# Interfaces_and_Connectors_-_Sensors.net
KiCad netlist of a schematic drawn in Altium Designer
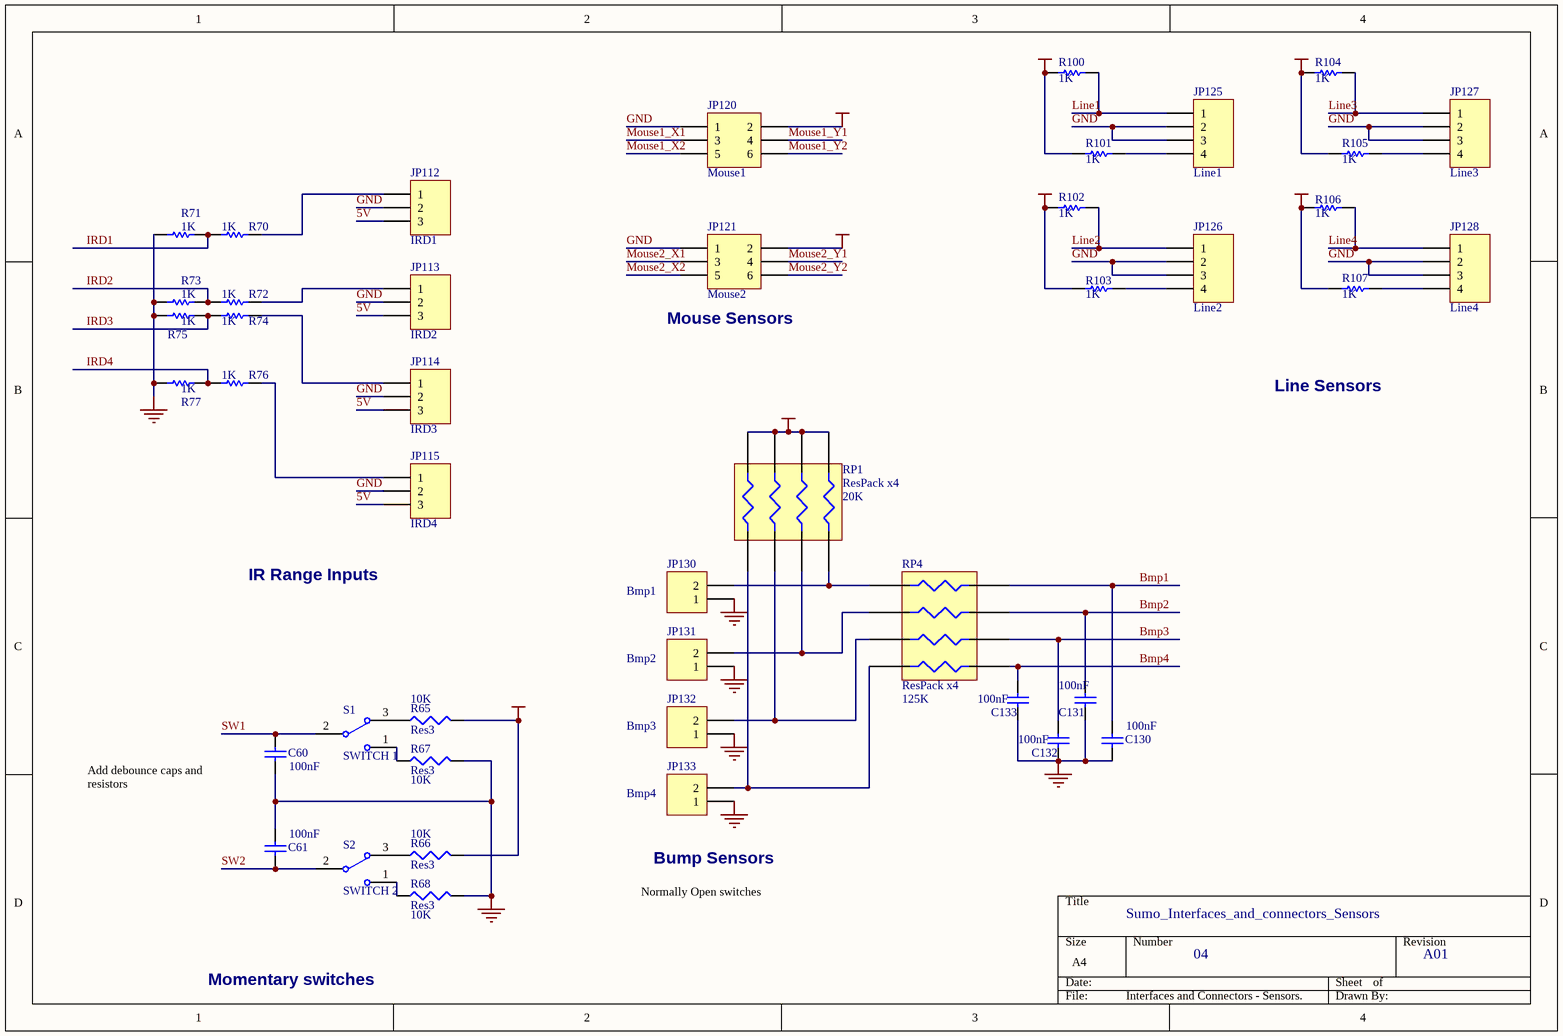
[diagram p0: Interfaces and Connectors - Sensors.SCHDOC]

(export (version "E")
  (design (tool "Eeschema 10.0.6"))
  (components
    (comp (ref "C60")
      (value "100nF")
      (footprint "CR2012-0805")
      (description "Capacitor (Semiconductor SIM Model)")
      (fields (field (name "Comment") "Cap Semi") (field (name "PUBLISHER") "Altium Limited"))
      (libsource (lib "Miscellaneous Devices") (part "Cap Semi"))
    )
    (comp (ref "C61")
      (value "100nF")
      (footprint "CR2012-0805")
      (description "Capacitor (Semiconductor SIM Model)")
      (fields (field (name "Comment") "Cap Semi") (field (name "PUBLISHER") "Altium Limited"))
      (libsource (lib "Miscellaneous Devices") (part "Cap Semi"))
    )
    (comp (ref "C130")
      (value "100nF")
      (footprint "CR2012-0805")
      (description "Capacitor (Semiconductor SIM Model)")
      (fields (field (name "Comment") "Cap Semi") (field (name "PUBLISHER") "Altium Limited"))
      (libsource (lib "Miscellaneous Devices") (part "Cap Semi"))
    )
    (comp (ref "C131")
      (value "100nF")
      (footprint "CR2012-0805")
      (description "Capacitor (Semiconductor SIM Model)")
      (fields (field (name "Comment") "Cap Semi") (field (name "PUBLISHER") "Altium Limited"))
      (libsource (lib "Miscellaneous Devices") (part "Cap Semi"))
    )
    (comp (ref "C132")
      (value "100nF")
      (footprint "CR2012-0805")
      (description "Capacitor (Semiconductor SIM Model)")
      (fields (field (name "Comment") "Cap Semi") (field (name "PUBLISHER") "Altium Limited"))
      (libsource (lib "Miscellaneous Devices") (part "Cap Semi"))
    )
    (comp (ref "C133")
      (value "100nF")
      (footprint "CR2012-0805")
      (description "Capacitor (Semiconductor SIM Model)")
      (fields (field (name "Comment") "Cap Semi") (field (name "PUBLISHER") "Altium Limited"))
      (libsource (lib "Miscellaneous Devices") (part "Cap Semi"))
    )
    (comp (ref "JP112")
      (value "IRD1")
      (footprint "ZHR 1x3 1.5mm")
      (description "Header, 3-Pin")
      (fields (field (name "PUBLISHER") "Altium Limited"))
      (libsource (lib "Miscellaneous Connectors") (part "MHDR1X3"))
    )
    (comp (ref "JP113")
      (value "IRD2")
      (footprint "ZHR 1x3 1.5mm")
      (description "Header, 3-Pin")
      (fields (field (name "PUBLISHER") "Altium Limited"))
      (libsource (lib "Miscellaneous Connectors") (part "MHDR1X3"))
    )
    (comp (ref "JP114")
      (value "IRD3")
      (footprint "ZHR 1x3 1.5mm")
      (description "Header, 3-Pin")
      (fields (field (name "PUBLISHER") "Altium Limited"))
      (libsource (lib "Miscellaneous Connectors") (part "MHDR1X3"))
    )
    (comp (ref "JP115")
      (value "IRD4")
      (footprint "ZHR 1x3 1.5mm")
      (description "Header, 3-Pin")
      (fields (field (name "PUBLISHER") "Altium Limited"))
      (libsource (lib "Miscellaneous Connectors") (part "MHDR1X3"))
    )
    (comp (ref "JP120")
      (value "Mouse1")
      (footprint "PHR 1x6 2mm")
      (description "Header, 3-Pin, Dual row")
      (fields (field (name "PUBLISHER") "Altium Limited"))
      (libsource (lib "Miscellaneous Connectors") (part "Header 3X2"))
    )
    (comp (ref "JP121")
      (value "Mouse2")
      (footprint "PHR 1x6 2mm")
      (description "Header, 3-Pin, Dual row")
      (fields (field (name "PUBLISHER") "Altium Limited"))
      (libsource (lib "Miscellaneous Connectors") (part "Header 3X2"))
    )
    (comp (ref "JP125")
      (value "Line1")
      (footprint "EHR 1x4 2.5mm")
      (description "Header, 4-Pin, Right Angle")
      (fields (field (name "PUBLISHER") "Altium Limited"))
      (libsource (lib "Miscellaneous Connectors") (part "Header 4H"))
    )
    (comp (ref "JP126")
      (value "Line2")
      (footprint "EHR 1x4 2.5mm")
      (description "Header, 4-Pin, Right Angle")
      (fields (field (name "PUBLISHER") "Altium Limited"))
      (libsource (lib "Miscellaneous Connectors") (part "Header 4H"))
    )
    (comp (ref "JP127")
      (value "Line3")
      (footprint "EHR 1x4 2.5mm")
      (description "Header, 4-Pin, Right Angle")
      (fields (field (name "PUBLISHER") "Altium Limited"))
      (libsource (lib "Miscellaneous Connectors") (part "Header 4H"))
    )
    (comp (ref "JP128")
      (value "Line4")
      (footprint "EHR 1x4 2.5mm")
      (description "Header, 4-Pin, Right Angle")
      (fields (field (name "PUBLISHER") "Altium Limited"))
      (libsource (lib "Miscellaneous Connectors") (part "Header 4H"))
    )
    (comp (ref "JP130")
      (value "Bmp1")
      (footprint "KK 1x2 2.54mm")
      (description "Header, 2-Pin")
      (fields (field (name "PUBLISHER") "Altium Limited"))
      (libsource (lib "Miscellaneous Connectors") (part "Header 2"))
    )
    (comp (ref "JP131")
      (value "Bmp2")
      (footprint "KK 1x2 2.54mm")
      (description "Header, 2-Pin")
      (fields (field (name "PUBLISHER") "Altium Limited"))
      (libsource (lib "Miscellaneous Connectors") (part "Header 2"))
    )
    (comp (ref "JP132")
      (value "Bmp3")
      (footprint "KK 1x2 2.54mm")
      (description "Header, 2-Pin")
      (fields (field (name "PUBLISHER") "Altium Limited"))
      (libsource (lib "Miscellaneous Connectors") (part "Header 2"))
    )
    (comp (ref "JP133")
      (value "Bmp4")
      (footprint "KK 1x2 2.54mm")
      (description "Header, 2-Pin")
      (fields (field (name "PUBLISHER") "Altium Limited"))
      (libsource (lib "Miscellaneous Connectors") (part "Header 2"))
    )
    (comp (ref "R65")
      (value "Res3")
      (footprint "R2012-0805")
      (description "Resistor")
      (fields (field (name "ALTIUM_VALUE") "10K") (field (name "PUBLISHER") "Altium Limited"))
      (libsource (lib "Miscellaneous Devices") (part "Res3"))
    )
    (comp (ref "R66")
      (value "Res3")
      (footprint "R2012-0805")
      (description "Resistor")
      (fields (field (name "ALTIUM_VALUE") "10K") (field (name "PUBLISHER") "Altium Limited"))
      (libsource (lib "Miscellaneous Devices") (part "Res3"))
    )
    (comp (ref "R67")
      (value "Res3")
      (footprint "R2012-0805")
      (description "Resistor")
      (fields (field (name "ALTIUM_VALUE") "10K") (field (name "PUBLISHER") "Altium Limited"))
      (libsource (lib "Miscellaneous Devices") (part "Res3"))
    )
    (comp (ref "R68")
      (value "Res3")
      (footprint "R2012-0805")
      (description "Resistor")
      (fields (field (name "ALTIUM_VALUE") "10K") (field (name "PUBLISHER") "Altium Limited"))
      (libsource (lib "Miscellaneous Devices") (part "Res3"))
    )
    (comp (ref "R70")
      (value "1K")
      (footprint "CR2012-0805")
      (description "Resistor")
      (fields (field (name "Comment") "Res1") (field (name "PUBLISHER") "Altium Limited"))
      (libsource (lib "Miscellaneous Devices") (part "Res1"))
    )
    (comp (ref "R71")
      (value "1K")
      (footprint "CR2012-0805")
      (description "Resistor")
      (fields (field (name "Comment") "Res1") (field (name "PUBLISHER") "Altium Limited"))
      (libsource (lib "Miscellaneous Devices") (part "Res1"))
    )
    (comp (ref "R72")
      (value "1K")
      (footprint "CR2012-0805")
      (description "Resistor")
      (fields (field (name "Comment") "Res1") (field (name "PUBLISHER") "Altium Limited"))
      (libsource (lib "Miscellaneous Devices") (part "Res1"))
    )
    (comp (ref "R73")
      (value "1K")
      (footprint "CR2012-0805")
      (description "Resistor")
      (fields (field (name "Comment") "Res1") (field (name "PUBLISHER") "Altium Limited"))
      (libsource (lib "Miscellaneous Devices") (part "Res1"))
    )
    (comp (ref "R74")
      (value "1K")
      (footprint "CR2012-0805")
      (description "Resistor")
      (fields (field (name "Comment") "Res1") (field (name "PUBLISHER") "Altium Limited"))
      (libsource (lib "Miscellaneous Devices") (part "Res1"))
    )
    (comp (ref "R75")
      (value "1K")
      (footprint "CR2012-0805")
      (description "Resistor")
      (fields (field (name "Comment") "Res1") (field (name "PUBLISHER") "Altium Limited"))
      (libsource (lib "Miscellaneous Devices") (part "Res1"))
    )
    (comp (ref "R76")
      (value "1K")
      (footprint "CR2012-0805")
      (description "Resistor")
      (fields (field (name "Comment") "Res1") (field (name "PUBLISHER") "Altium Limited"))
      (libsource (lib "Miscellaneous Devices") (part "Res1"))
    )
    (comp (ref "R77")
      (value "1K")
      (footprint "CR2012-0805")
      (description "Resistor")
      (fields (field (name "Comment") "Res1") (field (name "PUBLISHER") "Altium Limited"))
      (libsource (lib "Miscellaneous Devices") (part "Res1"))
    )
    (comp (ref "R100")
      (value "1K")
      (footprint "R2012-0805")
      (description "Resistor")
      (fields (field (name "Comment") "Res1") (field (name "PUBLISHER") "Altium Limited"))
      (libsource (lib "Miscellaneous Devices") (part "Res1"))
    )
    (comp (ref "R101")
      (value "1K")
      (footprint "R2012-0805")
      (description "Resistor")
      (fields (field (name "Comment") "Res1") (field (name "PUBLISHER") "Altium Limited"))
      (libsource (lib "Miscellaneous Devices") (part "Res1"))
    )
    (comp (ref "R102")
      (value "1K")
      (footprint "R2012-0805")
      (description "Resistor")
      (fields (field (name "Comment") "Res1") (field (name "PUBLISHER") "Altium Limited"))
      (libsource (lib "Miscellaneous Devices") (part "Res1"))
    )
    (comp (ref "R103")
      (value "1K")
      (footprint "R2012-0805")
      (description "Resistor")
      (fields (field (name "Comment") "Res1") (field (name "PUBLISHER") "Altium Limited"))
      (libsource (lib "Miscellaneous Devices") (part "Res1"))
    )
    (comp (ref "R104")
      (value "1K")
      (footprint "R2012-0805")
      (description "Resistor")
      (fields (field (name "Comment") "Res1") (field (name "PUBLISHER") "Altium Limited"))
      (libsource (lib "Miscellaneous Devices") (part "Res1"))
    )
    (comp (ref "R105")
      (value "1K")
      (footprint "R2012-0805")
      (description "Resistor")
      (fields (field (name "Comment") "Res1") (field (name "PUBLISHER") "Altium Limited"))
      (libsource (lib "Miscellaneous Devices") (part "Res1"))
    )
    (comp (ref "R106")
      (value "1K")
      (footprint "R2012-0805")
      (description "Resistor")
      (fields (field (name "Comment") "Res1") (field (name "PUBLISHER") "Altium Limited"))
      (libsource (lib "Miscellaneous Devices") (part "Res1"))
    )
    (comp (ref "R107")
      (value "1K")
      (footprint "R2012-0805")
      (description "Resistor")
      (fields (field (name "Comment") "Res1") (field (name "PUBLISHER") "Altium Limited"))
      (libsource (lib "Miscellaneous Devices") (part "Res1"))
    )
    (comp (ref "RP1")
      (value "ResPack x4")
      (footprint "4x0805 Resistor pack")
      (fields (field (name "ALTIUM_VALUE") "20K"))
      (libsource (lib "Sumo") (part "ResPack x4"))
    )
    (comp (ref "RP4")
      (value "ResPack x4")
      (footprint "4x0805 Resistor pack")
      (fields (field (name "ALTIUM_VALUE") "125K"))
      (libsource (lib "") (part "ResPack x4_1"))
    )
    (comp (ref "S1")
      (value "SWITCH 1")
      (footprint "SW SPDT")
      (description "SPDT Subminiature Toggle Switch, Right Angle Mounting, Vertical Actuation")
      (fields (field (name "PUBLISHER") "Altium Limited"))
      (libsource (lib "Miscellaneous Devices") (part "SW-SPDT"))
    )
    (comp (ref "S2")
      (value "SWITCH 2")
      (footprint "SW SPDT")
      (description "SPDT Subminiature Toggle Switch, Right Angle Mounting, Vertical Actuation")
      (fields (field (name "PUBLISHER") "Altium Limited"))
      (libsource (lib "Miscellaneous Devices") (part "SW-SPDT"))
    )
  )
  (nets
    (net (code "1") (name "/Bmp1") (class "Default")
      (node (ref "C130") (pin "2") (pinfunction "2_2") (pintype "passive"))
      (node (ref "RP4") (pin "8") (pintype "passive"))
    )
    (net (code "2") (name "/Bmp2") (class "Default")
      (node (ref "C131") (pin "2") (pinfunction "2_2") (pintype "passive"))
      (node (ref "RP4") (pin "7") (pintype "passive"))
    )
    (net (code "3") (name "/Bmp3") (class "Default")
      (node (ref "C132") (pin "2") (pinfunction "2_2") (pintype "passive"))
      (node (ref "RP4") (pin "6") (pintype "passive"))
    )
    (net (code "4") (name "/Bmp4") (class "Default")
      (node (ref "C133") (pin "2") (pinfunction "2_2") (pintype "passive"))
      (node (ref "RP4") (pin "5") (pintype "passive"))
    )
    (net (code "5") (name "/IRD1") (class "Default")
      (node (ref "R70") (pin "1") (pinfunction "1_1") (pintype "passive"))
      (node (ref "R71") (pin "2") (pinfunction "2_2") (pintype "passive"))
    )
    (net (code "6") (name "/IRD2") (class "Default")
      (node (ref "R72") (pin "1") (pinfunction "1_1") (pintype "passive"))
      (node (ref "R73") (pin "2") (pinfunction "2_2") (pintype "passive"))
    )
    (net (code "7") (name "/IRD3") (class "Default")
      (node (ref "R74") (pin "1") (pinfunction "1_1") (pintype "passive"))
      (node (ref "R75") (pin "2") (pinfunction "2_2") (pintype "passive"))
    )
    (net (code "8") (name "/IRD4") (class "Default")
      (node (ref "R76") (pin "1") (pinfunction "1_1") (pintype "passive"))
      (node (ref "R77") (pin "2") (pinfunction "2_2") (pintype "passive"))
    )
    (net (code "9") (name "/Line1") (class "Default")
      (node (ref "JP125") (pin "1") (pinfunction "1_1") (pintype "passive"))
      (node (ref "R100") (pin "2") (pinfunction "2_2") (pintype "passive"))
    )
    (net (code "10") (name "/Line2") (class "Default")
      (node (ref "JP126") (pin "1") (pinfunction "1_1") (pintype "passive"))
      (node (ref "R102") (pin "2") (pinfunction "2_2") (pintype "passive"))
    )
    (net (code "11") (name "/Line3") (class "Default")
      (node (ref "JP127") (pin "1") (pinfunction "1_1") (pintype "passive"))
      (node (ref "R104") (pin "2") (pinfunction "2_2") (pintype "passive"))
    )
    (net (code "12") (name "/Line4") (class "Default")
      (node (ref "JP128") (pin "1") (pinfunction "1_1") (pintype "passive"))
      (node (ref "R106") (pin "2") (pinfunction "2_2") (pintype "passive"))
    )
    (net (code "13") (name "/Mouse1_X1") (class "Default")
      (node (ref "JP120") (pin "3") (pinfunction "3_3") (pintype "passive"))
    )
    (net (code "14") (name "/Mouse1_X2") (class "Default")
      (node (ref "JP120") (pin "5") (pinfunction "5_5") (pintype "passive"))
    )
    (net (code "15") (name "/Mouse1_Y1") (class "Default")
      (node (ref "JP120") (pin "4") (pinfunction "4_4") (pintype "passive"))
    )
    (net (code "16") (name "/Mouse1_Y2") (class "Default")
      (node (ref "JP120") (pin "6") (pinfunction "6_6") (pintype "passive"))
    )
    (net (code "17") (name "/Mouse2_X1") (class "Default")
      (node (ref "JP121") (pin "3") (pinfunction "3_3") (pintype "passive"))
    )
    (net (code "18") (name "/Mouse2_X2") (class "Default")
      (node (ref "JP121") (pin "5") (pinfunction "5_5") (pintype "passive"))
    )
    (net (code "19") (name "/Mouse2_Y1") (class "Default")
      (node (ref "JP121") (pin "4") (pinfunction "4_4") (pintype "passive"))
    )
    (net (code "20") (name "/Mouse2_Y2") (class "Default")
      (node (ref "JP121") (pin "6") (pinfunction "6_6") (pintype "passive"))
    )
    (net (code "21") (name "/SW1") (class "Default")
      (node (ref "C60") (pin "2") (pinfunction "2_2") (pintype "passive"))
      (node (ref "S1") (pin "2") (pintype "passive"))
    )
    (net (code "22") (name "/SW2") (class "Default")
      (node (ref "C61") (pin "1") (pinfunction "1_1") (pintype "passive"))
      (node (ref "S2") (pin "2") (pintype "passive"))
    )
    (net (code "23") (name "5V") (class "Default")
      (node (ref "JP112") (pin "3") (pinfunction "3_3") (pintype "passive"))
      (node (ref "JP113") (pin "3") (pinfunction "3_3") (pintype "passive"))
      (node (ref "JP114") (pin "3") (pinfunction "3_3") (pintype "passive"))
      (node (ref "JP115") (pin "3") (pinfunction "3_3") (pintype "passive"))
      (node (ref "JP120") (pin "2") (pinfunction "2_2") (pintype "passive"))
      (node (ref "JP121") (pin "2") (pinfunction "2_2") (pintype "passive"))
      (node (ref "R100") (pin "1") (pinfunction "1_1") (pintype "passive"))
      (node (ref "R101") (pin "1") (pinfunction "1_1") (pintype "passive"))
      (node (ref "R102") (pin "1") (pinfunction "1_1") (pintype "passive"))
      (node (ref "R103") (pin "1") (pinfunction "1_1") (pintype "passive"))
      (node (ref "R104") (pin "1") (pinfunction "1_1") (pintype "passive"))
      (node (ref "R105") (pin "1") (pinfunction "1_1") (pintype "passive"))
      (node (ref "R106") (pin "1") (pinfunction "1_1") (pintype "passive"))
      (node (ref "R107") (pin "1") (pinfunction "1_1") (pintype "passive"))
      (node (ref "R65") (pin "2") (pinfunction "2_2") (pintype "passive"))
      (node (ref "R66") (pin "2") (pinfunction "2_2") (pintype "passive"))
      (node (ref "RP1") (pin "5") (pintype "passive"))
      (node (ref "RP1") (pin "6") (pintype "passive"))
      (node (ref "RP1") (pin "7") (pintype "passive"))
      (node (ref "RP1") (pin "8") (pintype "passive"))
    )
    (net (code "24") (name "GND") (class "Default")
      (node (ref "C130") (pin "1") (pinfunction "1_1") (pintype "passive"))
      (node (ref "C131") (pin "1") (pinfunction "1_1") (pintype "passive"))
      (node (ref "C132") (pin "1") (pinfunction "1_1") (pintype "passive"))
      (node (ref "C133") (pin "1") (pinfunction "1_1") (pintype "passive"))
      (node (ref "C60") (pin "1") (pinfunction "1_1") (pintype "passive"))
      (node (ref "C61") (pin "2") (pinfunction "2_2") (pintype "passive"))
      (node (ref "JP112") (pin "2") (pinfunction "2_2") (pintype "passive"))
      (node (ref "JP113") (pin "2") (pinfunction "2_2") (pintype "passive"))
      (node (ref "JP114") (pin "2") (pinfunction "2_2") (pintype "passive"))
      (node (ref "JP115") (pin "2") (pinfunction "2_2") (pintype "passive"))
      (node (ref "JP120") (pin "1") (pinfunction "1_1") (pintype "passive"))
      (node (ref "JP121") (pin "1") (pinfunction "1_1") (pintype "passive"))
      (node (ref "JP125") (pin "2") (pinfunction "2_2") (pintype "passive"))
      (node (ref "JP125") (pin "3") (pinfunction "3_3") (pintype "passive"))
      (node (ref "JP126") (pin "2") (pinfunction "2_2") (pintype "passive"))
      (node (ref "JP126") (pin "3") (pinfunction "3_3") (pintype "passive"))
      (node (ref "JP127") (pin "2") (pinfunction "2_2") (pintype "passive"))
      (node (ref "JP127") (pin "3") (pinfunction "3_3") (pintype "passive"))
      (node (ref "JP128") (pin "2") (pinfunction "2_2") (pintype "passive"))
      (node (ref "JP128") (pin "3") (pinfunction "3_3") (pintype "passive"))
      (node (ref "JP130") (pin "1") (pinfunction "1_1") (pintype "passive"))
      (node (ref "JP131") (pin "1") (pinfunction "1_1") (pintype "passive"))
      (node (ref "JP132") (pin "1") (pinfunction "1_1") (pintype "passive"))
      (node (ref "JP133") (pin "1") (pinfunction "1_1") (pintype "passive"))
      (node (ref "R67") (pin "2") (pinfunction "2_2") (pintype "passive"))
      (node (ref "R68") (pin "2") (pinfunction "2_2") (pintype "passive"))
      (node (ref "R71") (pin "1") (pinfunction "1_1") (pintype "passive"))
      (node (ref "R73") (pin "1") (pinfunction "1_1") (pintype "passive"))
      (node (ref "R75") (pin "1") (pinfunction "1_1") (pintype "passive"))
      (node (ref "R77") (pin "1") (pinfunction "1_1") (pintype "passive"))
    )
    (net (code "25") (name "Net-(JP112-Pad1)") (class "Default")
      (node (ref "JP112") (pin "1") (pinfunction "1_1") (pintype "passive"))
      (node (ref "R70") (pin "2") (pinfunction "2_2") (pintype "passive"))
    )
    (net (code "26") (name "Net-(JP113-Pad1)") (class "Default")
      (node (ref "JP113") (pin "1") (pinfunction "1_1") (pintype "passive"))
      (node (ref "R72") (pin "2") (pinfunction "2_2") (pintype "passive"))
    )
    (net (code "27") (name "Net-(JP114-Pad1)") (class "Default")
      (node (ref "JP114") (pin "1") (pinfunction "1_1") (pintype "passive"))
      (node (ref "R74") (pin "2") (pinfunction "2_2") (pintype "passive"))
    )
    (net (code "28") (name "Net-(JP115-Pad1)") (class "Default")
      (node (ref "JP115") (pin "1") (pinfunction "1_1") (pintype "passive"))
      (node (ref "R76") (pin "2") (pinfunction "2_2") (pintype "passive"))
    )
    (net (code "29") (name "Net-(JP125-Pad4)") (class "Default")
      (node (ref "JP125") (pin "4") (pinfunction "4_4") (pintype "passive"))
      (node (ref "R101") (pin "2") (pinfunction "2_2") (pintype "passive"))
    )
    (net (code "30") (name "Net-(JP126-Pad4)") (class "Default")
      (node (ref "JP126") (pin "4") (pinfunction "4_4") (pintype "passive"))
      (node (ref "R103") (pin "2") (pinfunction "2_2") (pintype "passive"))
    )
    (net (code "31") (name "Net-(JP127-Pad4)") (class "Default")
      (node (ref "JP127") (pin "4") (pinfunction "4_4") (pintype "passive"))
      (node (ref "R105") (pin "2") (pinfunction "2_2") (pintype "passive"))
    )
    (net (code "32") (name "Net-(JP128-Pad4)") (class "Default")
      (node (ref "JP128") (pin "4") (pinfunction "4_4") (pintype "passive"))
      (node (ref "R107") (pin "2") (pinfunction "2_2") (pintype "passive"))
    )
    (net (code "33") (name "Net-(JP130-Pad2)") (class "Default")
      (node (ref "JP130") (pin "2") (pinfunction "2_2") (pintype "passive"))
      (node (ref "RP1") (pin "4") (pintype "passive"))
      (node (ref "RP4") (pin "1") (pintype "passive"))
    )
    (net (code "34") (name "Net-(JP131-Pad2)") (class "Default")
      (node (ref "JP131") (pin "2") (pinfunction "2_2") (pintype "passive"))
      (node (ref "RP1") (pin "3") (pintype "passive"))
      (node (ref "RP4") (pin "2") (pintype "passive"))
    )
    (net (code "35") (name "Net-(JP132-Pad2)") (class "Default")
      (node (ref "JP132") (pin "2") (pinfunction "2_2") (pintype "passive"))
      (node (ref "RP1") (pin "2") (pintype "passive"))
      (node (ref "RP4") (pin "3") (pintype "passive"))
    )
    (net (code "36") (name "Net-(JP133-Pad2)") (class "Default")
      (node (ref "JP133") (pin "2") (pinfunction "2_2") (pintype "passive"))
      (node (ref "RP1") (pin "1") (pintype "passive"))
      (node (ref "RP4") (pin "4") (pintype "passive"))
    )
    (net (code "37") (name "Net-(R65-Pad1)") (class "Default")
      (node (ref "R65") (pin "1") (pinfunction "1_1") (pintype "passive"))
      (node (ref "S1") (pin "3") (pintype "passive"))
    )
    (net (code "38") (name "Net-(R66-Pad1)") (class "Default")
      (node (ref "R66") (pin "1") (pinfunction "1_1") (pintype "passive"))
      (node (ref "S2") (pin "3") (pintype "passive"))
    )
    (net (code "39") (name "Net-(R67-Pad1)") (class "Default")
      (node (ref "R67") (pin "1") (pinfunction "1_1") (pintype "passive"))
      (node (ref "S1") (pin "1") (pintype "passive"))
    )
    (net (code "40") (name "Net-(R68-Pad1)") (class "Default")
      (node (ref "R68") (pin "1") (pinfunction "1_1") (pintype "passive"))
      (node (ref "S2") (pin "1") (pintype "passive"))
    )
  )
)
